# 11_HUB_USB3_0.net
KiCad netlist of a schematic drawn in Altium Designer
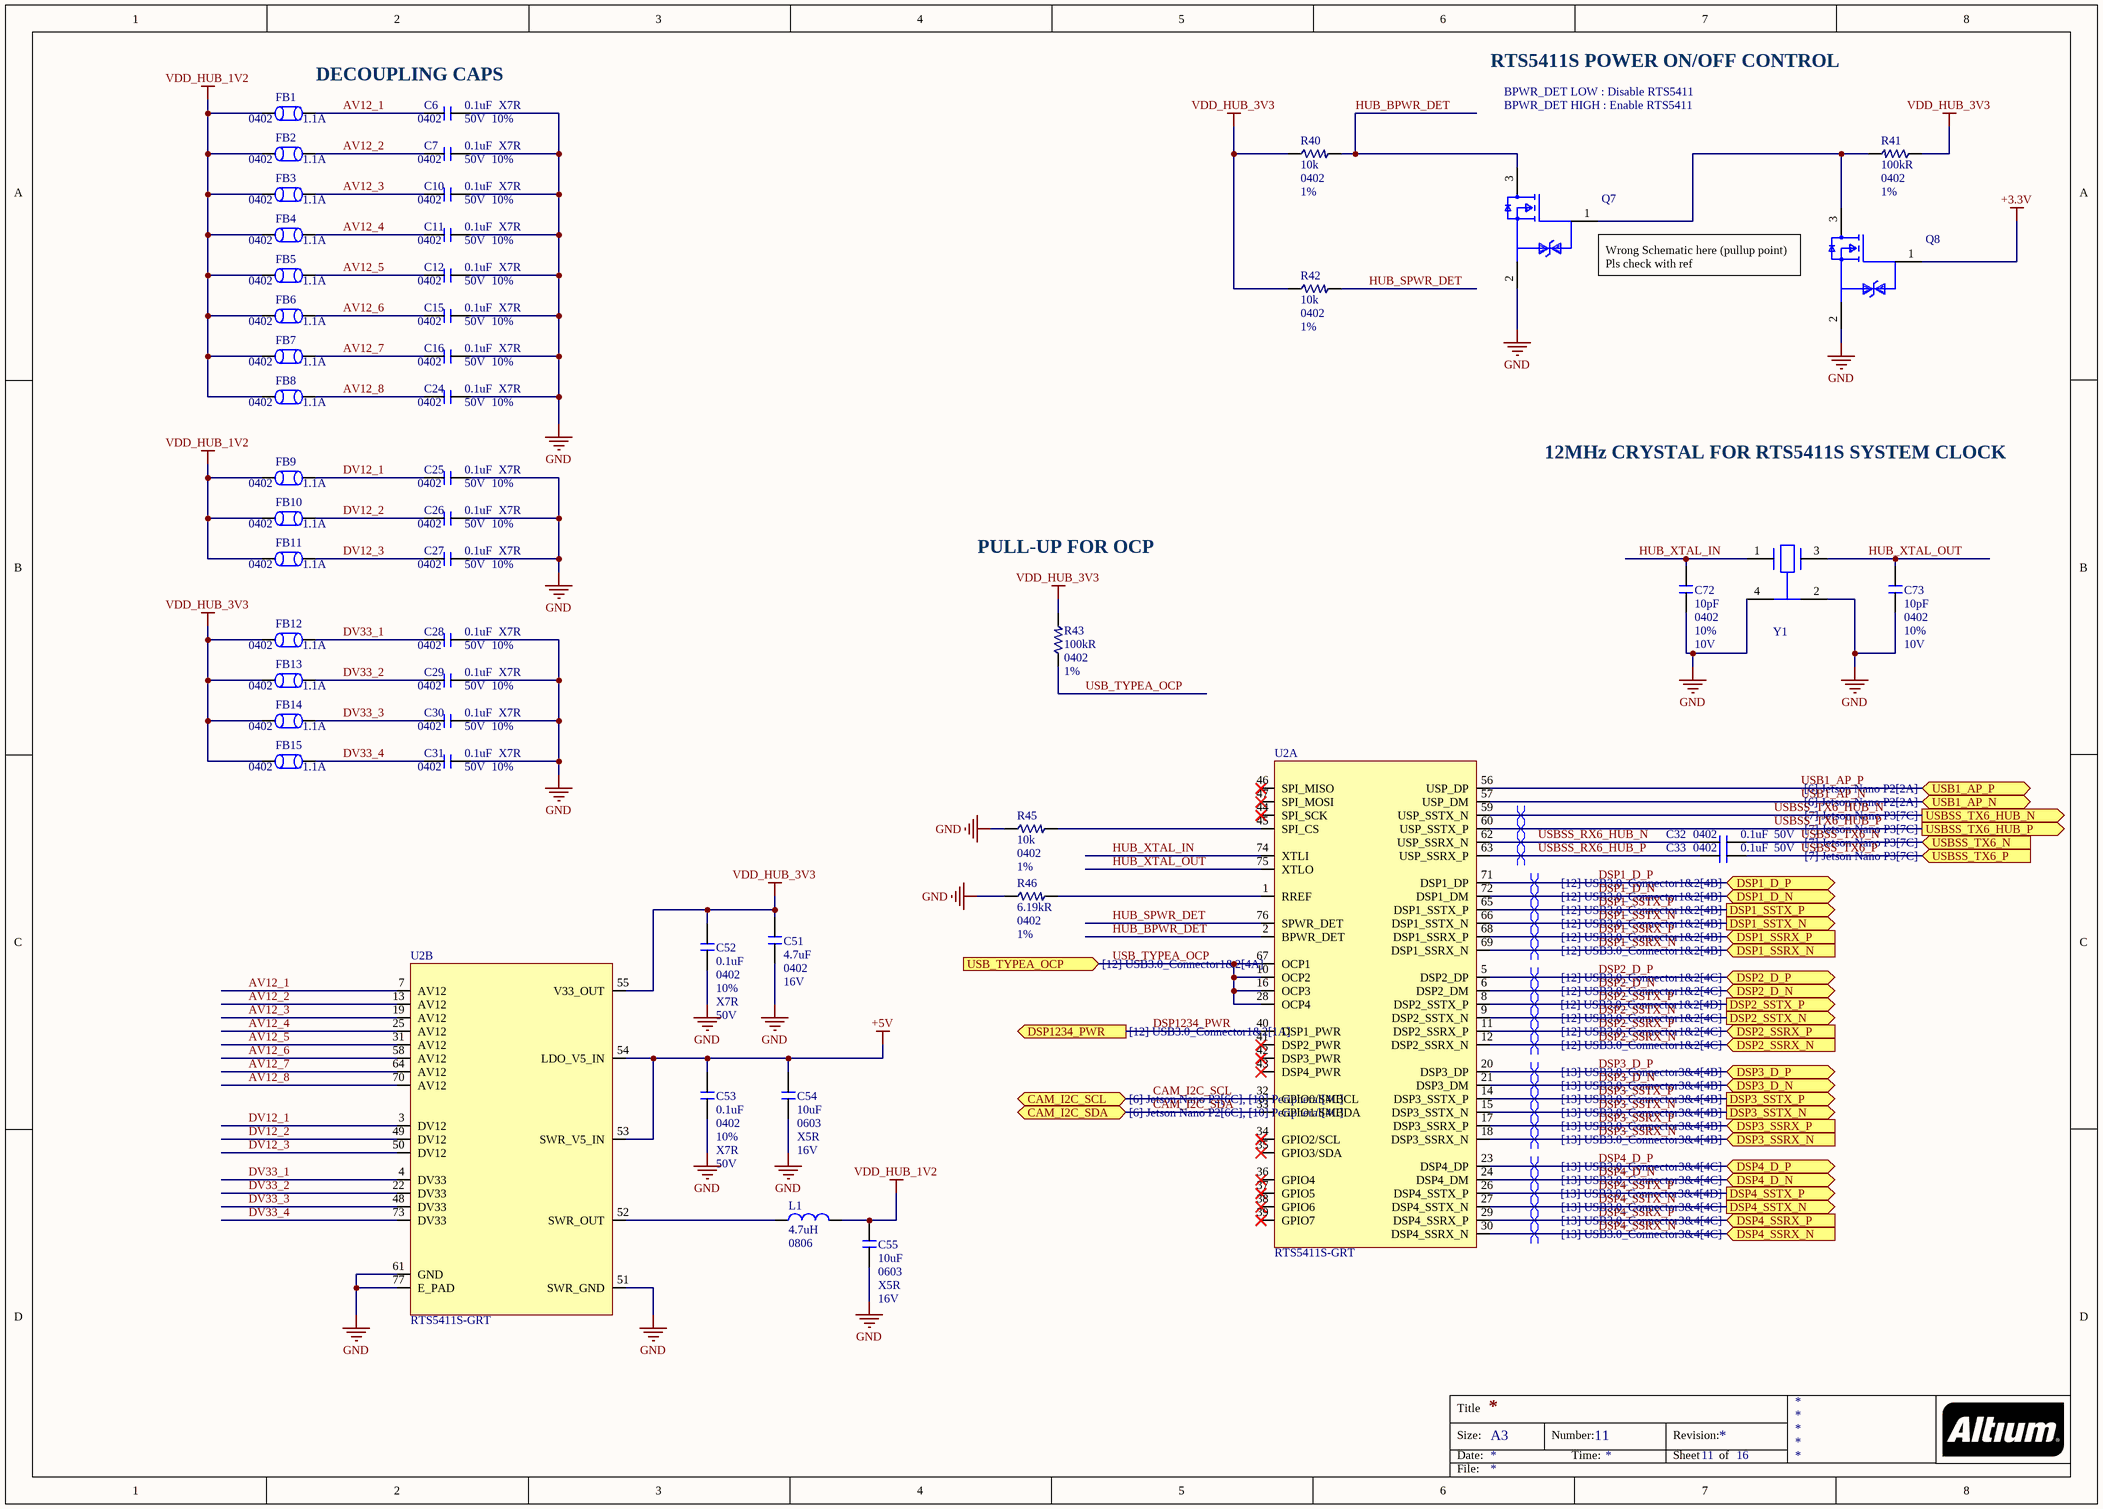
[diagram p0: [11] HUB USB3.0.SchDoc]

(export (version "E")
  (design (tool "Eeschema 10.0.6"))
  (components
    (comp (ref "C6")
      (value "0.1uF")
      (footprint "C0402M")
      (description "CAP CER 0.1UF 50V X7R 0402")
      (fields
        (field (name "MANUFACTURER") "Murata")
        (field (name "MANUFACTURER PART NUMBER") "GRM155R71H104KE14D")
        (field (name "CASE/PACKAGE") "0402")
        (field (name "TOLERANCE") "10%")
        (field (name "DIELECTRIC") "X7R")
        (field (name "VOLTAGE") "50V")
      )
      (libsource (lib "CommonLib") (part "CAP_CER"))
    )
    (comp (ref "C7")
      (value "0.1uF")
      (footprint "C0402M")
      (description "CAP CER 0.1UF 50V X7R 0402")
      (fields
        (field (name "MANUFACTURER") "Murata")
        (field (name "MANUFACTURER PART NUMBER") "GRM155R71H104KE14D")
        (field (name "CASE/PACKAGE") "0402")
        (field (name "TOLERANCE") "10%")
        (field (name "DIELECTRIC") "X7R")
        (field (name "VOLTAGE") "50V")
      )
      (libsource (lib "CommonLib") (part "CAP_CER"))
    )
    (comp (ref "C10")
      (value "0.1uF")
      (footprint "C0402M")
      (description "CAP CER 0.1UF 50V X7R 0402")
      (fields
        (field (name "MANUFACTURER") "Murata")
        (field (name "MANUFACTURER PART NUMBER") "GRM155R71H104KE14D")
        (field (name "CASE/PACKAGE") "0402")
        (field (name "TOLERANCE") "10%")
        (field (name "DIELECTRIC") "X7R")
        (field (name "VOLTAGE") "50V")
      )
      (libsource (lib "CommonLib") (part "CAP_CER"))
    )
    (comp (ref "C11")
      (value "0.1uF")
      (footprint "C0402M")
      (description "CAP CER 0.1UF 50V X7R 0402")
      (fields
        (field (name "MANUFACTURER") "Murata")
        (field (name "MANUFACTURER PART NUMBER") "GRM155R71H104KE14D")
        (field (name "CASE/PACKAGE") "0402")
        (field (name "TOLERANCE") "10%")
        (field (name "DIELECTRIC") "X7R")
        (field (name "VOLTAGE") "50V")
      )
      (libsource (lib "CommonLib") (part "CAP_CER"))
    )
    (comp (ref "C12")
      (value "0.1uF")
      (footprint "C0402M")
      (description "CAP CER 0.1UF 50V X7R 0402")
      (fields
        (field (name "MANUFACTURER") "Murata")
        (field (name "MANUFACTURER PART NUMBER") "GRM155R71H104KE14D")
        (field (name "CASE/PACKAGE") "0402")
        (field (name "TOLERANCE") "10%")
        (field (name "DIELECTRIC") "X7R")
        (field (name "VOLTAGE") "50V")
      )
      (libsource (lib "CommonLib") (part "CAP_CER"))
    )
    (comp (ref "C15")
      (value "0.1uF")
      (footprint "C0402M")
      (description "CAP CER 0.1UF 50V X7R 0402")
      (fields
        (field (name "MANUFACTURER") "Murata")
        (field (name "MANUFACTURER PART NUMBER") "GRM155R71H104KE14D")
        (field (name "CASE/PACKAGE") "0402")
        (field (name "TOLERANCE") "10%")
        (field (name "DIELECTRIC") "X7R")
        (field (name "VOLTAGE") "50V")
      )
      (libsource (lib "CommonLib") (part "CAP_CER"))
    )
    (comp (ref "C16")
      (value "0.1uF")
      (footprint "C0402M")
      (description "CAP CER 0.1UF 50V X7R 0402")
      (fields
        (field (name "MANUFACTURER") "Murata")
        (field (name "MANUFACTURER PART NUMBER") "GRM155R71H104KE14D")
        (field (name "CASE/PACKAGE") "0402")
        (field (name "TOLERANCE") "10%")
        (field (name "DIELECTRIC") "X7R")
        (field (name "VOLTAGE") "50V")
      )
      (libsource (lib "CommonLib") (part "CAP_CER"))
    )
    (comp (ref "C24")
      (value "0.1uF")
      (footprint "C0402M")
      (description "CAP CER 0.1UF 50V X7R 0402")
      (fields
        (field (name "MANUFACTURER") "Murata")
        (field (name "MANUFACTURER PART NUMBER") "GRM155R71H104KE14D")
        (field (name "CASE/PACKAGE") "0402")
        (field (name "TOLERANCE") "10%")
        (field (name "DIELECTRIC") "X7R")
        (field (name "VOLTAGE") "50V")
      )
      (libsource (lib "CommonLib") (part "CAP_CER"))
    )
    (comp (ref "C25")
      (value "0.1uF")
      (footprint "C0402M")
      (description "CAP CER 0.1UF 50V X7R 0402")
      (fields
        (field (name "MANUFACTURER") "Murata")
        (field (name "MANUFACTURER PART NUMBER") "GRM155R71H104KE14D")
        (field (name "CASE/PACKAGE") "0402")
        (field (name "TOLERANCE") "10%")
        (field (name "DIELECTRIC") "X7R")
        (field (name "VOLTAGE") "50V")
      )
      (libsource (lib "CommonLib") (part "CAP_CER"))
    )
    (comp (ref "C26")
      (value "0.1uF")
      (footprint "C0402M")
      (description "CAP CER 0.1UF 50V X7R 0402")
      (fields
        (field (name "MANUFACTURER") "Murata")
        (field (name "MANUFACTURER PART NUMBER") "GRM155R71H104KE14D")
        (field (name "CASE/PACKAGE") "0402")
        (field (name "TOLERANCE") "10%")
        (field (name "DIELECTRIC") "X7R")
        (field (name "VOLTAGE") "50V")
      )
      (libsource (lib "CommonLib") (part "CAP_CER"))
    )
    (comp (ref "C27")
      (value "0.1uF")
      (footprint "C0402M")
      (description "CAP CER 0.1UF 50V X7R 0402")
      (fields
        (field (name "MANUFACTURER") "Murata")
        (field (name "MANUFACTURER PART NUMBER") "GRM155R71H104KE14D")
        (field (name "CASE/PACKAGE") "0402")
        (field (name "TOLERANCE") "10%")
        (field (name "DIELECTRIC") "X7R")
        (field (name "VOLTAGE") "50V")
      )
      (libsource (lib "CommonLib") (part "CAP_CER"))
    )
    (comp (ref "C28")
      (value "0.1uF")
      (footprint "C0402M")
      (description "CAP CER 0.1UF 50V X7R 0402")
      (fields
        (field (name "MANUFACTURER") "Murata")
        (field (name "MANUFACTURER PART NUMBER") "GRM155R71H104KE14D")
        (field (name "CASE/PACKAGE") "0402")
        (field (name "TOLERANCE") "10%")
        (field (name "DIELECTRIC") "X7R")
        (field (name "VOLTAGE") "50V")
      )
      (libsource (lib "CommonLib") (part "CAP_CER"))
    )
    (comp (ref "C29")
      (value "0.1uF")
      (footprint "C0402M")
      (description "CAP CER 0.1UF 50V X7R 0402")
      (fields
        (field (name "MANUFACTURER") "Murata")
        (field (name "MANUFACTURER PART NUMBER") "GRM155R71H104KE14D")
        (field (name "CASE/PACKAGE") "0402")
        (field (name "TOLERANCE") "10%")
        (field (name "DIELECTRIC") "X7R")
        (field (name "VOLTAGE") "50V")
      )
      (libsource (lib "CommonLib") (part "CAP_CER"))
    )
    (comp (ref "C30")
      (value "0.1uF")
      (footprint "C0402M")
      (description "CAP CER 0.1UF 50V X7R 0402")
      (fields
        (field (name "MANUFACTURER") "Murata")
        (field (name "MANUFACTURER PART NUMBER") "GRM155R71H104KE14D")
        (field (name "CASE/PACKAGE") "0402")
        (field (name "TOLERANCE") "10%")
        (field (name "DIELECTRIC") "X7R")
        (field (name "VOLTAGE") "50V")
      )
      (libsource (lib "CommonLib") (part "CAP_CER"))
    )
    (comp (ref "C31")
      (value "0.1uF")
      (footprint "C0402M")
      (description "CAP CER 0.1UF 50V X7R 0402")
      (fields
        (field (name "MANUFACTURER") "Murata")
        (field (name "MANUFACTURER PART NUMBER") "GRM155R71H104KE14D")
        (field (name "CASE/PACKAGE") "0402")
        (field (name "TOLERANCE") "10%")
        (field (name "DIELECTRIC") "X7R")
        (field (name "VOLTAGE") "50V")
      )
      (libsource (lib "CommonLib") (part "CAP_CER"))
    )
    (comp (ref "C32")
      (value "0.1uF")
      (footprint "C0402M")
      (description "CAP CER 0.1UF 50V X7R 0402")
      (fields
        (field (name "MANUFACTURER") "Murata")
        (field (name "MANUFACTURER PART NUMBER") "GRM155R71H104KE14D")
        (field (name "CASE/PACKAGE") "0402")
        (field (name "VOLTAGE") "50V")
      )
      (libsource (lib "CommonLib") (part "CAP_CER"))
    )
    (comp (ref "C33")
      (value "0.1uF")
      (footprint "C0402M")
      (description "CAP CER 0.1UF 50V X7R 0402")
      (fields
        (field (name "MANUFACTURER") "Murata")
        (field (name "MANUFACTURER PART NUMBER") "GRM155R71H104KE14D")
        (field (name "CASE/PACKAGE") "0402")
        (field (name "VOLTAGE") "50V")
      )
      (libsource (lib "CommonLib") (part "CAP_CER"))
    )
    (comp (ref "C51")
      (value "4.7uF")
      (footprint "C0402M")
      (description "CAP CER 4.7UF 16V X5R 0402")
      (fields
        (field (name "MANUFACTURER") "Samsung")
        (field (name "MANUFACTURER PART NUMBER") "CL05A475MO5NUNC")
        (field (name "CASE/PACKAGE") "0402")
        (field (name "VOLTAGE RATING") "16V")
      )
      (libsource (lib "CommonLib") (part "CAP_CER"))
    )
    (comp (ref "C52")
      (value "0.1uF")
      (footprint "C0402M")
      (description "CAP CER 0.1UF 50V X7R 0402")
      (fields
        (field (name "MANUFACTURER") "Murata")
        (field (name "MANUFACTURER PART NUMBER") "GRM155R71H104KE14D")
        (field (name "CASE/PACKAGE") "0402")
        (field (name "TOLERANCE") "10%")
        (field (name "DIELECTRIC") "X7R")
        (field (name "VOLTAGE") "50V")
      )
      (libsource (lib "CommonLib") (part "CAP_CER"))
    )
    (comp (ref "C53")
      (value "0.1uF")
      (footprint "C0402M")
      (description "CAP CER 0.1UF 50V X7R 0402")
      (fields
        (field (name "MANUFACTURER") "Murata")
        (field (name "MANUFACTURER PART NUMBER") "GRM155R71H104KE14D")
        (field (name "CASE/PACKAGE") "0402")
        (field (name "TOLERANCE") "10%")
        (field (name "DIELECTRIC") "X7R")
        (field (name "VOLTAGE") "50V")
      )
      (libsource (lib "CommonLib") (part "CAP_CER"))
    )
    (comp (ref "C54")
      (value "10uF")
      (footprint "C0603M")
      (description "CAP CER 10UF 16V X5R 0603")
      (fields
        (field (name "MANUFACTURER") "Taiyo Yuden")
        (field (name "MANUFACTURER PART NUMBER") "EMK107BBJ106MA-T")
        (field (name "CASE/PACKAGE") "0603")
        (field (name "DIELECTRIC") "X5R")
        (field (name "VOLTAGE RATING (DC)") "16V")
      )
      (libsource (lib "CommonLib") (part "CAP_CER"))
    )
    (comp (ref "C55")
      (value "10uF")
      (footprint "C0603M")
      (description "CAP CER 10UF 16V X5R 0603")
      (fields
        (field (name "MANUFACTURER") "Taiyo Yuden")
        (field (name "MANUFACTURER PART NUMBER") "EMK107BBJ106MA-T")
        (field (name "CASE/PACKAGE") "0603")
        (field (name "DIELECTRIC") "X5R")
        (field (name "VOLTAGE RATING (DC)") "16V")
      )
      (libsource (lib "CommonLib") (part "CAP_CER"))
    )
    (comp (ref "C72")
      (value "10pF")
      (footprint "C0402M")
      (fields
        (field (name "CASE/PACKAGE") "0402")
        (field (name "TOLERANCE") "10%")
        (field (name "VOLTAGE RATING") "10V")
      )
      (libsource (lib "CommonLib") (part "CAP_CER"))
    )
    (comp (ref "C73")
      (value "10pF")
      (footprint "C0402M")
      (fields
        (field (name "CASE/PACKAGE") "0402")
        (field (name "TOLERANCE") "10%")
        (field (name "VOLTAGE RATING") "10V")
      )
      (libsource (lib "CommonLib") (part "CAP_CER"))
    )
    (comp (ref "FB1")
      (value "BLM15AX300SN1D")
      (footprint "R0402M")
      (description "0402 30Ω ±25% DCR=0.06Ω 1.1A 应用：信号线与电源线-超低直流电阻")
      (fields
        (field (name "CASE CODE (IMPERIAL)") "0402")
        (field (name "TOLERANCE") "25%")
        (field (name "CURRENT RATING") "1.1A")
      )
      (libsource (lib "CommonLib") (part "FB"))
    )
    (comp (ref "FB2")
      (value "BLM15AX300SN1D")
      (footprint "R0402M")
      (description "0402 30Ω ±25% DCR=0.06Ω 1.1A 应用：信号线与电源线-超低直流电阻")
      (fields
        (field (name "CASE CODE (IMPERIAL)") "0402")
        (field (name "TOLERANCE") "25%")
        (field (name "CURRENT RATING") "1.1A")
      )
      (libsource (lib "CommonLib") (part "FB"))
    )
    (comp (ref "FB3")
      (value "BLM15AX300SN1D")
      (footprint "R0402M")
      (description "0402 30Ω ±25% DCR=0.06Ω 1.1A 应用：信号线与电源线-超低直流电阻")
      (fields
        (field (name "CASE CODE (IMPERIAL)") "0402")
        (field (name "TOLERANCE") "25%")
        (field (name "CURRENT RATING") "1.1A")
      )
      (libsource (lib "CommonLib") (part "FB"))
    )
    (comp (ref "FB4")
      (value "BLM15AX300SN1D")
      (footprint "R0402M")
      (description "0402 30Ω ±25% DCR=0.06Ω 1.1A 应用：信号线与电源线-超低直流电阻")
      (fields
        (field (name "CASE CODE (IMPERIAL)") "0402")
        (field (name "TOLERANCE") "25%")
        (field (name "CURRENT RATING") "1.1A")
      )
      (libsource (lib "CommonLib") (part "FB"))
    )
    (comp (ref "FB5")
      (value "BLM15AX300SN1D")
      (footprint "R0402M")
      (description "0402 30Ω ±25% DCR=0.06Ω 1.1A 应用：信号线与电源线-超低直流电阻")
      (fields
        (field (name "CASE CODE (IMPERIAL)") "0402")
        (field (name "TOLERANCE") "25%")
        (field (name "CURRENT RATING") "1.1A")
      )
      (libsource (lib "CommonLib") (part "FB"))
    )
    (comp (ref "FB6")
      (value "BLM15AX300SN1D")
      (footprint "R0402M")
      (description "0402 30Ω ±25% DCR=0.06Ω 1.1A 应用：信号线与电源线-超低直流电阻")
      (fields
        (field (name "CASE CODE (IMPERIAL)") "0402")
        (field (name "TOLERANCE") "25%")
        (field (name "CURRENT RATING") "1.1A")
      )
      (libsource (lib "CommonLib") (part "FB"))
    )
    (comp (ref "FB7")
      (value "BLM15AX300SN1D")
      (footprint "R0402M")
      (description "0402 30Ω ±25% DCR=0.06Ω 1.1A 应用：信号线与电源线-超低直流电阻")
      (fields
        (field (name "CASE CODE (IMPERIAL)") "0402")
        (field (name "TOLERANCE") "25%")
        (field (name "CURRENT RATING") "1.1A")
      )
      (libsource (lib "CommonLib") (part "FB"))
    )
    (comp (ref "FB8")
      (value "BLM15AX300SN1D")
      (footprint "R0402M")
      (description "0402 30Ω ±25% DCR=0.06Ω 1.1A 应用：信号线与电源线-超低直流电阻")
      (fields
        (field (name "CASE CODE (IMPERIAL)") "0402")
        (field (name "TOLERANCE") "25%")
        (field (name "CURRENT RATING") "1.1A")
      )
      (libsource (lib "CommonLib") (part "FB"))
    )
    (comp (ref "FB9")
      (value "BLM15AX300SN1D")
      (footprint "R0402M")
      (description "0402 30Ω ±25% DCR=0.06Ω 1.1A 应用：信号线与电源线-超低直流电阻")
      (fields
        (field (name "CASE CODE (IMPERIAL)") "0402")
        (field (name "TOLERANCE") "25%")
        (field (name "CURRENT RATING") "1.1A")
      )
      (libsource (lib "CommonLib") (part "FB"))
    )
    (comp (ref "FB10")
      (value "BLM15AX300SN1D")
      (footprint "R0402M")
      (description "0402 30Ω ±25% DCR=0.06Ω 1.1A 应用：信号线与电源线-超低直流电阻")
      (fields
        (field (name "CASE CODE (IMPERIAL)") "0402")
        (field (name "TOLERANCE") "25%")
        (field (name "CURRENT RATING") "1.1A")
      )
      (libsource (lib "CommonLib") (part "FB"))
    )
    (comp (ref "FB11")
      (value "BLM15AX300SN1D")
      (footprint "R0402M")
      (description "0402 30Ω ±25% DCR=0.06Ω 1.1A 应用：信号线与电源线-超低直流电阻")
      (fields
        (field (name "CASE CODE (IMPERIAL)") "0402")
        (field (name "TOLERANCE") "25%")
        (field (name "CURRENT RATING") "1.1A")
      )
      (libsource (lib "CommonLib") (part "FB"))
    )
    (comp (ref "FB12")
      (value "BLM15AX300SN1D")
      (footprint "R0402M")
      (description "0402 30Ω ±25% DCR=0.06Ω 1.1A 应用：信号线与电源线-超低直流电阻")
      (fields
        (field (name "CASE CODE (IMPERIAL)") "0402")
        (field (name "TOLERANCE") "25%")
        (field (name "CURRENT RATING") "1.1A")
      )
      (libsource (lib "CommonLib") (part "FB"))
    )
    (comp (ref "FB13")
      (value "BLM15AX300SN1D")
      (footprint "R0402M")
      (description "0402 30Ω ±25% DCR=0.06Ω 1.1A 应用：信号线与电源线-超低直流电阻")
      (fields
        (field (name "CASE CODE (IMPERIAL)") "0402")
        (field (name "TOLERANCE") "25%")
        (field (name "CURRENT RATING") "1.1A")
      )
      (libsource (lib "CommonLib") (part "FB"))
    )
    (comp (ref "FB14")
      (value "BLM15AX300SN1D")
      (footprint "R0402M")
      (description "0402 30Ω ±25% DCR=0.06Ω 1.1A 应用：信号线与电源线-超低直流电阻")
      (fields
        (field (name "CASE CODE (IMPERIAL)") "0402")
        (field (name "TOLERANCE") "25%")
        (field (name "CURRENT RATING") "1.1A")
      )
      (libsource (lib "CommonLib") (part "FB"))
    )
    (comp (ref "FB15")
      (value "BLM15AX300SN1D")
      (footprint "R0402M")
      (description "0402 30Ω ±25% DCR=0.06Ω 1.1A 应用：信号线与电源线-超低直流电阻")
      (fields
        (field (name "CASE CODE (IMPERIAL)") "0402")
        (field (name "TOLERANCE") "25%")
        (field (name "CURRENT RATING") "1.1A")
      )
      (libsource (lib "CommonLib") (part "FB"))
    )
    (comp (ref "L1")
      (value "4.7uH")
      (footprint "IND_0805")
      (description "0806 4.7uH ±30% DCR=0.175Ω 0.8A SRF=20MHz")
      (fields (field (name "CASE CODE (IMPERIAL)") "0806") (field (name "TOLERANCE") "30%"))
      (libsource (lib "CommonLib") (part "IND_SMD"))
    )
    (comp (ref "Q7")
      (value "DMN26D0UFB4-7")
      (footprint "Diodes_Inc_X2-DFN1006-3_MFG")
      (description "N沟道 VDS=20V VGS=±10V ID=240mA P=350mW")
      (libsource (lib "Schlib1") (part "DMN26D0UFB4-7"))
    )
    (comp (ref "Q8")
      (value "DMN26D0UFB4-7")
      (footprint "Diodes_Inc_X2-DFN1006-3_MFG")
      (description "N沟道 VDS=20V VGS=±10V ID=240mA P=350mW")
      (libsource (lib "Schlib1") (part "DMN26D0UFB4-7"))
    )
    (comp (ref "R40")
      (value "10k")
      (footprint "R0402M")
      (description "RES SMD 10K OHM 1% 1/16W 0402")
      (fields
        (field (name "MANUFACTURER") "Yageo")
        (field (name "MANUFACTURER PART NUMBER") "RC0402FR-0710KL")
        (field (name "CASE CODE (IMPERIAL)") "0402")
        (field (name "TOLERANCE") "1%")
      )
      (libsource (lib "CommonLib") (part "RES_SMD"))
    )
    (comp (ref "R41")
      (value "100kR")
      (footprint "R0402M")
      (description "贴片电阻 100000Ω ± 1.00% 0.0625W ± 100ppm/℃ 0402")
      (fields (field (name "CASE/PACKAGE") "0402") (field (name "TOLERANCE") "1%"))
      (libsource (lib "CommonLib") (part "RES_SMD"))
    )
    (comp (ref "R42")
      (value "10k")
      (footprint "R0402M")
      (description "RES SMD 10K OHM 1% 1/16W 0402")
      (fields
        (field (name "MANUFACTURER") "Yageo")
        (field (name "MANUFACTURER PART NUMBER") "RC0402FR-0710KL")
        (field (name "CASE CODE (IMPERIAL)") "0402")
        (field (name "TOLERANCE") "1%")
      )
      (libsource (lib "CommonLib") (part "RES_SMD"))
    )
    (comp (ref "R43")
      (value "100kR")
      (footprint "R0402M")
      (description "贴片电阻 100000Ω ± 1.00% 0.0625W ± 100ppm/℃ 0402")
      (fields (field (name "CASE/PACKAGE") "0402") (field (name "TOLERANCE") "1%"))
      (libsource (lib "CommonLib") (part "RES_SMD"))
    )
    (comp (ref "R45")
      (value "10k")
      (footprint "R0402M")
      (description "RES SMD 10K OHM 1% 1/16W 0402")
      (fields
        (field (name "MANUFACTURER") "Yageo")
        (field (name "MANUFACTURER PART NUMBER") "RC0402FR-0710KL")
        (field (name "CASE CODE (IMPERIAL)") "0402")
        (field (name "TOLERANCE") "1%")
      )
      (libsource (lib "CommonLib") (part "RES_SMD"))
    )
    (comp (ref "R46")
      (value "6.19kR")
      (footprint "R0402M")
      (description "贴片电阻 6190Ω ± 1.00% 0.0625W ± 100ppm/℃ 0402")
      (fields (field (name "CASE/PACKAGE") "0402") (field (name "TOLERANCE") "1%"))
      (libsource (lib "CommonLib") (part "RES_SMD"))
    )
    (comp (ref "U2")
      (value "RTS5411S-GRT")
      (footprint "QFN40P900X900X90_HS-77N")
      (description "USB 3.0 Super-Speed HUB")
      (libsource (lib "Schlib1") (part "RTS5411S-GRT"))
    )
    (comp (ref "Y1")
      (value "ABM8G-12.000MHZ-4Y-T3")
      (footprint "Abracon_ABM8G_0")
      (description "12MHz ±30ppm 晶体 10pF 120 欧姆 -10°C ~ 60°C  表面贴装 4-SMD，无引线（DFN，LCC）")
      (libsource (lib "Schlib1") (part "ABM8G-12.000MHZ-4Y-T3"))
    )
  )
  (nets
    (net (code "1") (name "+3.3V") (class "Default")
      (node (ref "Q8") (pin "1") (pinfunction "G_1") (pintype "passive"))
    )
    (net (code "2") (name "+5V") (class "Default")
      (node (ref "C53") (pin "1") (pinfunction "1_1") (pintype "passive"))
      (node (ref "C54") (pin "2") (pinfunction "2_2") (pintype "passive"))
      (node (ref "U2") (pin "53") (pinfunction "SWR_V5_IN_53") (pintype "passive"))
      (node (ref "U2") (pin "54") (pinfunction "LDO_V5_IN_54") (pintype "passive"))
    )
    (net (code "3") (name "/AV12_1") (class "Default")
      (node (ref "C6") (pin "1") (pinfunction "1_1") (pintype "passive"))
      (node (ref "FB1") (pin "1") (pinfunction "1_1") (pintype "passive"))
      (node (ref "U2") (pin "7") (pinfunction "AV12_7") (pintype "passive"))
    )
    (net (code "4") (name "/AV12_2") (class "Default")
      (node (ref "C7") (pin "1") (pinfunction "1_1") (pintype "passive"))
      (node (ref "FB2") (pin "1") (pinfunction "1_1") (pintype "passive"))
      (node (ref "U2") (pin "13") (pinfunction "AV12_13") (pintype "passive"))
    )
    (net (code "5") (name "/AV12_3") (class "Default")
      (node (ref "C10") (pin "1") (pinfunction "1_1") (pintype "passive"))
      (node (ref "FB3") (pin "1") (pinfunction "1_1") (pintype "passive"))
      (node (ref "U2") (pin "19") (pinfunction "AV12_19") (pintype "passive"))
    )
    (net (code "6") (name "/AV12_4") (class "Default")
      (node (ref "C11") (pin "1") (pinfunction "1_1") (pintype "passive"))
      (node (ref "FB4") (pin "1") (pinfunction "1_1") (pintype "passive"))
      (node (ref "U2") (pin "25") (pinfunction "AV12_25") (pintype "passive"))
    )
    (net (code "7") (name "/AV12_5") (class "Default")
      (node (ref "C12") (pin "1") (pinfunction "1_1") (pintype "passive"))
      (node (ref "FB5") (pin "1") (pinfunction "1_1") (pintype "passive"))
      (node (ref "U2") (pin "31") (pinfunction "AV12_31") (pintype "passive"))
    )
    (net (code "8") (name "/AV12_6") (class "Default")
      (node (ref "C15") (pin "1") (pinfunction "1_1") (pintype "passive"))
      (node (ref "FB6") (pin "1") (pinfunction "1_1") (pintype "passive"))
      (node (ref "U2") (pin "58") (pinfunction "AV12_58") (pintype "passive"))
    )
    (net (code "9") (name "/AV12_7") (class "Default")
      (node (ref "C16") (pin "1") (pinfunction "1_1") (pintype "passive"))
      (node (ref "FB7") (pin "1") (pinfunction "1_1") (pintype "passive"))
      (node (ref "U2") (pin "64") (pinfunction "AV12_64") (pintype "passive"))
    )
    (net (code "10") (name "/AV12_8") (class "Default")
      (node (ref "C24") (pin "1") (pinfunction "1_1") (pintype "passive"))
      (node (ref "FB8") (pin "1") (pinfunction "1_1") (pintype "passive"))
      (node (ref "U2") (pin "70") (pinfunction "AV12_70") (pintype "passive"))
    )
    (net (code "11") (name "/CAM_I2C_SCL") (class "Default")
      (node (ref "U2") (pin "32") (pinfunction "GPIO0/SMBCL_32") (pintype "passive"))
    )
    (net (code "12") (name "/CAM_I2C_SDA") (class "Default")
      (node (ref "U2") (pin "33") (pinfunction "GPIO1/SMBDA_33") (pintype "passive"))
    )
    (net (code "13") (name "/DSP1_D_N") (class "Default")
      (node (ref "U2") (pin "72") (pinfunction "DSP1_DM_72") (pintype "passive"))
    )
    (net (code "14") (name "/DSP1_D_P") (class "Default")
      (node (ref "U2") (pin "71") (pinfunction "DSP1_DP_71") (pintype "passive"))
    )
    (net (code "15") (name "/DSP1_SSRX_N") (class "Default")
      (node (ref "U2") (pin "69") (pinfunction "DSP1_SSRX_N_69") (pintype "passive"))
    )
    (net (code "16") (name "/DSP1_SSRX_P") (class "Default")
      (node (ref "U2") (pin "68") (pinfunction "DSP1_SSRX_P_68") (pintype "passive"))
    )
    (net (code "17") (name "/DSP1_SSTX_N") (class "Default")
      (node (ref "U2") (pin "66") (pinfunction "DSP1_SSTX_N_66") (pintype "passive"))
    )
    (net (code "18") (name "/DSP1_SSTX_P") (class "Default")
      (node (ref "U2") (pin "65") (pinfunction "DSP1_SSTX_P_65") (pintype "passive"))
    )
    (net (code "19") (name "/DSP2_D_N") (class "Default")
      (node (ref "U2") (pin "6") (pinfunction "DSP2_DM_6") (pintype "passive"))
    )
    (net (code "20") (name "/DSP2_D_P") (class "Default")
      (node (ref "U2") (pin "5") (pinfunction "DSP2_DP_5") (pintype "passive"))
    )
    (net (code "21") (name "/DSP2_SSRX_N") (class "Default")
      (node (ref "U2") (pin "12") (pinfunction "DSP2_SSRX_N_12") (pintype "passive"))
    )
    (net (code "22") (name "/DSP2_SSRX_P") (class "Default")
      (node (ref "U2") (pin "11") (pinfunction "DSP2_SSRX_P_11") (pintype "passive"))
    )
    (net (code "23") (name "/DSP2_SSTX_N") (class "Default")
      (node (ref "U2") (pin "9") (pinfunction "DSP2_SSTX_N_9") (pintype "passive"))
    )
    (net (code "24") (name "/DSP2_SSTX_P") (class "Default")
      (node (ref "U2") (pin "8") (pinfunction "DSP2_SSTX_P_8") (pintype "passive"))
    )
    (net (code "25") (name "/DSP3_D_N") (class "Default")
      (node (ref "U2") (pin "21") (pinfunction "DSP3_DM_21") (pintype "passive"))
    )
    (net (code "26") (name "/DSP3_D_P") (class "Default")
      (node (ref "U2") (pin "20") (pinfunction "DSP3_DP_20") (pintype "passive"))
    )
    (net (code "27") (name "/DSP3_SSRX_N") (class "Default")
      (node (ref "U2") (pin "18") (pinfunction "DSP3_SSRX_N_18") (pintype "passive"))
    )
    (net (code "28") (name "/DSP3_SSRX_P") (class "Default")
      (node (ref "U2") (pin "17") (pinfunction "DSP3_SSRX_P_17") (pintype "passive"))
    )
    (net (code "29") (name "/DSP3_SSTX_N") (class "Default")
      (node (ref "U2") (pin "15") (pinfunction "DSP3_SSTX_N_15") (pintype "passive"))
    )
    (net (code "30") (name "/DSP3_SSTX_P") (class "Default")
      (node (ref "U2") (pin "14") (pinfunction "DSP3_SSTX_P_14") (pintype "passive"))
    )
    (net (code "31") (name "/DSP4_D_N") (class "Default")
      (node (ref "U2") (pin "24") (pinfunction "DSP4_DM_24") (pintype "passive"))
    )
    (net (code "32") (name "/DSP4_D_P") (class "Default")
      (node (ref "U2") (pin "23") (pinfunction "DSP4_DP_23") (pintype "passive"))
    )
    (net (code "33") (name "/DSP4_SSRX_N") (class "Default")
      (node (ref "U2") (pin "30") (pinfunction "DSP4_SSRX_N_30") (pintype "passive"))
    )
    (net (code "34") (name "/DSP4_SSRX_P") (class "Default")
      (node (ref "U2") (pin "29") (pinfunction "DSP4_SSRX_P_29") (pintype "passive"))
    )
    (net (code "35") (name "/DSP4_SSTX_N") (class "Default")
      (node (ref "U2") (pin "27") (pinfunction "DSP4_SSTX_N_27") (pintype "passive"))
    )
    (net (code "36") (name "/DSP4_SSTX_P") (class "Default")
      (node (ref "U2") (pin "26") (pinfunction "DSP4_SSTX_P_26") (pintype "passive"))
    )
    (net (code "37") (name "/DSP1234_PWR") (class "Default")
      (node (ref "U2") (pin "40") (pinfunction "DSP1_PWR_40") (pintype "passive"))
    )
    (net (code "38") (name "/DV12_1") (class "Default")
      (node (ref "C25") (pin "1") (pinfunction "1_1") (pintype "passive"))
      (node (ref "FB9") (pin "1") (pinfunction "1_1") (pintype "passive"))
      (node (ref "U2") (pin "3") (pinfunction "DV12_3") (pintype "passive"))
    )
    (net (code "39") (name "/DV12_2") (class "Default")
      (node (ref "C26") (pin "1") (pinfunction "1_1") (pintype "passive"))
      (node (ref "FB10") (pin "1") (pinfunction "1_1") (pintype "passive"))
      (node (ref "U2") (pin "49") (pinfunction "DV12_49") (pintype "passive"))
    )
    (net (code "40") (name "/DV12_3") (class "Default")
      (node (ref "C27") (pin "1") (pinfunction "1_1") (pintype "passive"))
      (node (ref "FB11") (pin "1") (pinfunction "1_1") (pintype "passive"))
      (node (ref "U2") (pin "50") (pinfunction "DV12_50") (pintype "passive"))
    )
    (net (code "41") (name "/DV33_1") (class "Default")
      (node (ref "C28") (pin "1") (pinfunction "1_1") (pintype "passive"))
      (node (ref "FB12") (pin "1") (pinfunction "1_1") (pintype "passive"))
      (node (ref "U2") (pin "4") (pinfunction "DV33_4") (pintype "passive"))
    )
    (net (code "42") (name "/DV33_2") (class "Default")
      (node (ref "C29") (pin "1") (pinfunction "1_1") (pintype "passive"))
      (node (ref "FB13") (pin "1") (pinfunction "1_1") (pintype "passive"))
      (node (ref "U2") (pin "22") (pinfunction "DV33_22") (pintype "passive"))
    )
    (net (code "43") (name "/DV33_3") (class "Default")
      (node (ref "C30") (pin "1") (pinfunction "1_1") (pintype "passive"))
      (node (ref "FB14") (pin "1") (pinfunction "1_1") (pintype "passive"))
      (node (ref "U2") (pin "48") (pinfunction "DV33_48") (pintype "passive"))
    )
    (net (code "44") (name "/DV33_4") (class "Default")
      (node (ref "C31") (pin "1") (pinfunction "1_1") (pintype "passive"))
      (node (ref "FB15") (pin "1") (pinfunction "1_1") (pintype "passive"))
      (node (ref "U2") (pin "73") (pinfunction "DV33_73") (pintype "passive"))
    )
    (net (code "45") (name "/HUB_BPWR_DET") (class "Default")
      (node (ref "Q7") (pin "3") (pinfunction "D_3") (pintype "passive"))
      (node (ref "R40") (pin "1") (pinfunction "1_1") (pintype "passive"))
      (node (ref "U2") (pin "2") (pinfunction "BPWR_DET_2") (pintype "passive"))
    )
    (net (code "46") (name "/HUB_SPWR_DET") (class "Default")
      (node (ref "R42") (pin "1") (pinfunction "1_1") (pintype "passive"))
      (node (ref "U2") (pin "76") (pinfunction "SPWR_DET_76") (pintype "passive"))
    )
    (net (code "47") (name "/HUB_XTAL_IN") (class "Default")
      (node (ref "C72") (pin "1") (pinfunction "1_1") (pintype "passive"))
      (node (ref "U2") (pin "74") (pinfunction "XTLI_74") (pintype "passive"))
      (node (ref "Y1") (pin "1") (pinfunction "1_1") (pintype "passive"))
    )
    (net (code "48") (name "/HUB_XTAL_OUT") (class "Default")
      (node (ref "C73") (pin "1") (pinfunction "1_1") (pintype "passive"))
      (node (ref "U2") (pin "75") (pinfunction "XTLO_75") (pintype "passive"))
      (node (ref "Y1") (pin "3") (pinfunction "3_3") (pintype "passive"))
    )
    (net (code "49") (name "/USB1_AP_N") (class "Default")
      (node (ref "U2") (pin "57") (pinfunction "USP_DM_57") (pintype "passive"))
    )
    (net (code "50") (name "/USB1_AP_P") (class "Default")
      (node (ref "U2") (pin "56") (pinfunction "USP_DP_56") (pintype "passive"))
    )
    (net (code "51") (name "/USBSS_RX6_HUB_N") (class "Default")
      (node (ref "C32") (pin "1") (pinfunction "1_1") (pintype "passive"))
      (node (ref "U2") (pin "62") (pinfunction "USP_SSRX_N_62") (pintype "passive"))
    )
    (net (code "52") (name "/USBSS_RX6_HUB_P") (class "Default")
      (node (ref "C33") (pin "1") (pinfunction "1_1") (pintype "passive"))
      (node (ref "U2") (pin "63") (pinfunction "USP_SSRX_P_63") (pintype "passive"))
    )
    (net (code "53") (name "/USBSS_TX6_HUB_N") (class "Default")
      (node (ref "U2") (pin "59") (pinfunction "USP_SSTX_N_59") (pintype "passive"))
    )
    (net (code "54") (name "/USBSS_TX6_HUB_P") (class "Default")
      (node (ref "U2") (pin "60") (pinfunction "USP_SSTX_P_60") (pintype "passive"))
    )
    (net (code "55") (name "/USBSS_TX6_N") (class "Default")
      (node (ref "C32") (pin "2") (pinfunction "2_2") (pintype "passive"))
    )
    (net (code "56") (name "/USBSS_TX6_P") (class "Default")
      (node (ref "C33") (pin "2") (pinfunction "2_2") (pintype "passive"))
    )
    (net (code "57") (name "/USB_TYPEA_OCP") (class "Default")
      (node (ref "R43") (pin "2") (pinfunction "2_2") (pintype "passive"))
      (node (ref "U2") (pin "10") (pinfunction "OCP2_10") (pintype "passive"))
      (node (ref "U2") (pin "16") (pinfunction "OCP3_16") (pintype "passive"))
      (node (ref "U2") (pin "28") (pinfunction "OCP4_28") (pintype "passive"))
      (node (ref "U2") (pin "67") (pinfunction "OCP1_67") (pintype "passive"))
    )
    (net (code "58") (name "GND") (class "Default")
      (node (ref "C10") (pin "2") (pinfunction "2_2") (pintype "passive"))
      (node (ref "C11") (pin "2") (pinfunction "2_2") (pintype "passive"))
      (node (ref "C12") (pin "2") (pinfunction "2_2") (pintype "passive"))
      (node (ref "C15") (pin "2") (pinfunction "2_2") (pintype "passive"))
      (node (ref "C16") (pin "2") (pinfunction "2_2") (pintype "passive"))
      (node (ref "C24") (pin "2") (pinfunction "2_2") (pintype "passive"))
      (node (ref "C25") (pin "2") (pinfunction "2_2") (pintype "passive"))
      (node (ref "C26") (pin "2") (pinfunction "2_2") (pintype "passive"))
      (node (ref "C27") (pin "2") (pinfunction "2_2") (pintype "passive"))
      (node (ref "C28") (pin "2") (pinfunction "2_2") (pintype "passive"))
      (node (ref "C29") (pin "2") (pinfunction "2_2") (pintype "passive"))
      (node (ref "C30") (pin "2") (pinfunction "2_2") (pintype "passive"))
      (node (ref "C31") (pin "2") (pinfunction "2_2") (pintype "passive"))
      (node (ref "C51") (pin "2") (pinfunction "2_2") (pintype "passive"))
      (node (ref "C52") (pin "2") (pinfunction "2_2") (pintype "passive"))
      (node (ref "C53") (pin "2") (pinfunction "2_2") (pintype "passive"))
      (node (ref "C54") (pin "1") (pinfunction "1_1") (pintype "passive"))
      (node (ref "C55") (pin "1") (pinfunction "1_1") (pintype "passive"))
      (node (ref "C6") (pin "2") (pinfunction "2_2") (pintype "passive"))
      (node (ref "C7") (pin "2") (pinfunction "2_2") (pintype "passive"))
      (node (ref "C72") (pin "2") (pinfunction "2_2") (pintype "passive"))
      (node (ref "C73") (pin "2") (pinfunction "2_2") (pintype "passive"))
      (node (ref "Q7") (pin "2") (pinfunction "S_2") (pintype "passive"))
      (node (ref "Q8") (pin "2") (pinfunction "S_2") (pintype "passive"))
      (node (ref "R45") (pin "2") (pinfunction "2_2") (pintype "passive"))
      (node (ref "R46") (pin "2") (pinfunction "2_2") (pintype "passive"))
      (node (ref "U2") (pin "51") (pinfunction "SWR_GND_51") (pintype "passive"))
      (node (ref "U2") (pin "61") (pinfunction "GND_61") (pintype "passive"))
      (node (ref "U2") (pin "77") (pinfunction "E_PAD_77") (pintype "passive"))
      (node (ref "Y1") (pin "2") (pinfunction "GND_2") (pintype "passive"))
      (node (ref "Y1") (pin "4") (pinfunction "GND_4") (pintype "passive"))
    )
    (net (code "59") (name "Net-(Q7-G)") (class "Default")
      (node (ref "Q7") (pin "1") (pinfunction "G_1") (pintype "passive"))
      (node (ref "Q8") (pin "3") (pinfunction "D_3") (pintype "passive"))
      (node (ref "R41") (pin "1") (pinfunction "1_1") (pintype "passive"))
    )
    (net (code "60") (name "Net-(U2A-RREF)") (class "Default")
      (node (ref "R46") (pin "1") (pinfunction "1_1") (pintype "passive"))
      (node (ref "U2") (pin "1") (pinfunction "RREF_1") (pintype "passive"))
    )
    (net (code "61") (name "Net-(U2A-SPI_CS)") (class "Default")
      (node (ref "R45") (pin "1") (pinfunction "1_1") (pintype "passive"))
      (node (ref "U2") (pin "45") (pinfunction "SPI_CS_45") (pintype "passive"))
    )
    (net (code "62") (name "Net-(U2B-SWR_OUT)") (class "Default")
      (node (ref "L1") (pin "1") (pinfunction "1_1") (pintype "passive"))
      (node (ref "U2") (pin "52") (pinfunction "SWR_OUT_52") (pintype "passive"))
    )
    (net (code "63") (name "VDD_HUB_1V2") (class "Default")
      (node (ref "C55") (pin "2") (pinfunction "2_2") (pintype "passive"))
      (node (ref "FB1") (pin "2") (pinfunction "2_2") (pintype "passive"))
      (node (ref "FB10") (pin "2") (pinfunction "2_2") (pintype "passive"))
      (node (ref "FB11") (pin "2") (pinfunction "2_2") (pintype "passive"))
      (node (ref "FB2") (pin "2") (pinfunction "2_2") (pintype "passive"))
      (node (ref "FB3") (pin "2") (pinfunction "2_2") (pintype "passive"))
      (node (ref "FB4") (pin "2") (pinfunction "2_2") (pintype "passive"))
      (node (ref "FB5") (pin "2") (pinfunction "2_2") (pintype "passive"))
      (node (ref "FB6") (pin "2") (pinfunction "2_2") (pintype "passive"))
      (node (ref "FB7") (pin "2") (pinfunction "2_2") (pintype "passive"))
      (node (ref "FB8") (pin "2") (pinfunction "2_2") (pintype "passive"))
      (node (ref "FB9") (pin "2") (pinfunction "2_2") (pintype "passive"))
      (node (ref "L1") (pin "2") (pinfunction "2_2") (pintype "passive"))
    )
    (net (code "64") (name "VDD_HUB_3V3") (class "Default")
      (node (ref "C51") (pin "1") (pinfunction "1_1") (pintype "passive"))
      (node (ref "C52") (pin "1") (pinfunction "1_1") (pintype "passive"))
      (node (ref "FB12") (pin "2") (pinfunction "2_2") (pintype "passive"))
      (node (ref "FB13") (pin "2") (pinfunction "2_2") (pintype "passive"))
      (node (ref "FB14") (pin "2") (pinfunction "2_2") (pintype "passive"))
      (node (ref "FB15") (pin "2") (pinfunction "2_2") (pintype "passive"))
      (node (ref "R40") (pin "2") (pinfunction "2_2") (pintype "passive"))
      (node (ref "R41") (pin "2") (pinfunction "2_2") (pintype "passive"))
      (node (ref "R42") (pin "2") (pinfunction "2_2") (pintype "passive"))
      (node (ref "R43") (pin "1") (pinfunction "1_1") (pintype "passive"))
      (node (ref "U2") (pin "55") (pinfunction "V33_OUT_55") (pintype "passive"))
    )
    (net (code "65") (name "unconnected-(U2A-DSP2_PWR-Pad41)") (class "Default")
      (node (ref "U2") (pin "41") (pinfunction "DSP2_PWR_41") (pintype "passive+no_connect"))
    )
    (net (code "66") (name "unconnected-(U2A-DSP3_PWR-Pad42)") (class "Default")
      (node (ref "U2") (pin "42") (pinfunction "DSP3_PWR_42") (pintype "passive+no_connect"))
    )
    (net (code "67") (name "unconnected-(U2A-DSP4_PWR-Pad43)") (class "Default")
      (node (ref "U2") (pin "43") (pinfunction "DSP4_PWR_43") (pintype "passive+no_connect"))
    )
    (net (code "68") (name "unconnected-(U2A-GPIO2{slash}SCL-Pad34)") (class "Default")
      (node (ref "U2") (pin "34") (pinfunction "GPIO2/SCL_34") (pintype "passive+no_connect"))
    )
    (net (code "69") (name "unconnected-(U2A-GPIO3{slash}SDA-Pad35)") (class "Default")
      (node (ref "U2") (pin "35") (pinfunction "GPIO3/SDA_35") (pintype "passive+no_connect"))
    )
    (net (code "70") (name "unconnected-(U2A-GPIO4-Pad36)") (class "Default")
      (node (ref "U2") (pin "36") (pinfunction "GPIO4_36") (pintype "passive+no_connect"))
    )
    (net (code "71") (name "unconnected-(U2A-GPIO5-Pad37)") (class "Default")
      (node (ref "U2") (pin "37") (pinfunction "GPIO5_37") (pintype "passive+no_connect"))
    )
    (net (code "72") (name "unconnected-(U2A-GPIO6-Pad38)") (class "Default")
      (node (ref "U2") (pin "38") (pinfunction "GPIO6_38") (pintype "passive+no_connect"))
    )
    (net (code "73") (name "unconnected-(U2A-GPIO7-Pad39)") (class "Default")
      (node (ref "U2") (pin "39") (pinfunction "GPIO7_39") (pintype "passive+no_connect"))
    )
    (net (code "74") (name "unconnected-(U2A-SPI_MISO-Pad46)") (class "Default")
      (node (ref "U2") (pin "46") (pinfunction "SPI_MISO_46") (pintype "passive+no_connect"))
    )
    (net (code "75") (name "unconnected-(U2A-SPI_MOSI-Pad47)") (class "Default")
      (node (ref "U2") (pin "47") (pinfunction "SPI_MOSI_47") (pintype "passive+no_connect"))
    )
    (net (code "76") (name "unconnected-(U2A-SPI_SCK-Pad44)") (class "Default")
      (node (ref "U2") (pin "44") (pinfunction "SPI_SCK_44") (pintype "passive+no_connect"))
    )
  )
)
